# TFT.net
KiCad netlist of a schematic drawn in Altium Designer
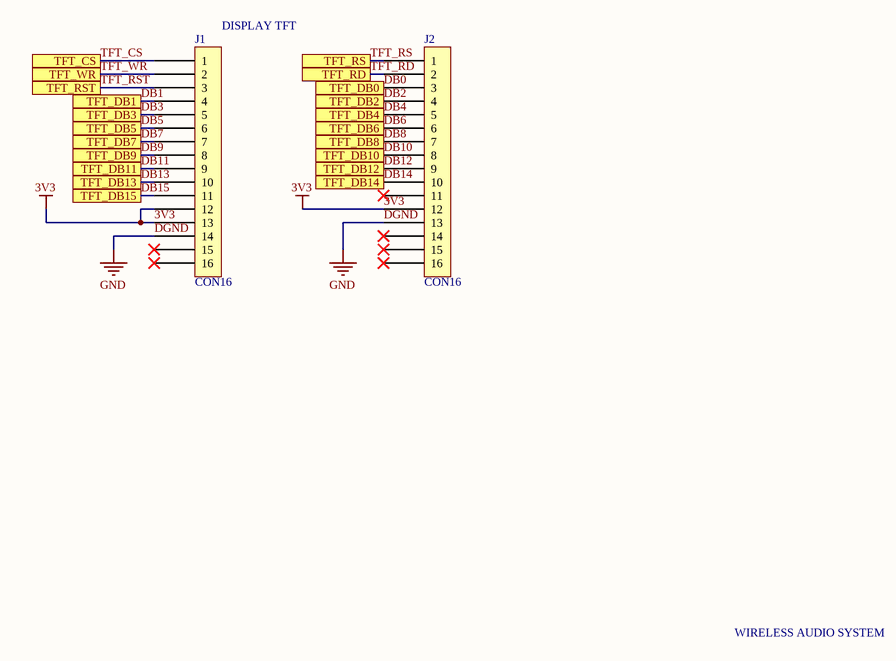
[diagram p0: TFT.SchDoc]

(export (version "E")
  (design (tool "Eeschema 10.0.6"))
  (components
    (comp (ref "J1")
      (value "CON16")
      (footprint "HDR1X16")
      (libsource (lib "Miscellaneous Connectors") (part "CON16"))
    )
    (comp (ref "J2")
      (value "CON16")
      (footprint "HDR1X16")
      (libsource (lib "Miscellaneous Connectors") (part "CON16"))
    )
  )
  (nets
    (net (code "1") (name "/DB0") (class "Default")
      (node (ref "J2") (pin "3") (pinfunction "3_3") (pintype "passive"))
    )
    (net (code "2") (name "/DB1") (class "Default")
      (node (ref "J1") (pin "4") (pinfunction "4_4") (pintype "passive"))
    )
    (net (code "3") (name "/DB2") (class "Default")
      (node (ref "J2") (pin "4") (pinfunction "4_4") (pintype "passive"))
    )
    (net (code "4") (name "/DB3") (class "Default")
      (node (ref "J1") (pin "5") (pinfunction "5_5") (pintype "passive"))
    )
    (net (code "5") (name "/DB4") (class "Default")
      (node (ref "J2") (pin "5") (pinfunction "5_5") (pintype "passive"))
    )
    (net (code "6") (name "/DB5") (class "Default")
      (node (ref "J1") (pin "6") (pinfunction "6_6") (pintype "passive"))
    )
    (net (code "7") (name "/DB6") (class "Default")
      (node (ref "J2") (pin "6") (pinfunction "6_6") (pintype "passive"))
    )
    (net (code "8") (name "/DB7") (class "Default")
      (node (ref "J1") (pin "7") (pinfunction "7_7") (pintype "passive"))
    )
    (net (code "9") (name "/DB8") (class "Default")
      (node (ref "J2") (pin "7") (pinfunction "7_7") (pintype "passive"))
    )
    (net (code "10") (name "/DB9") (class "Default")
      (node (ref "J1") (pin "8") (pinfunction "8_8") (pintype "passive"))
    )
    (net (code "11") (name "/DB10") (class "Default")
      (node (ref "J2") (pin "8") (pinfunction "8_8") (pintype "passive"))
    )
    (net (code "12") (name "/DB11") (class "Default")
      (node (ref "J1") (pin "9") (pinfunction "9_9") (pintype "passive"))
    )
    (net (code "13") (name "/DB12") (class "Default")
      (node (ref "J2") (pin "9") (pinfunction "9_9") (pintype "passive"))
    )
    (net (code "14") (name "/DB13") (class "Default")
      (node (ref "J1") (pin "10") (pinfunction "10_10") (pintype "passive"))
    )
    (net (code "15") (name "/DB14") (class "Default")
      (node (ref "J2") (pin "10") (pinfunction "10_10") (pintype "passive"))
    )
    (net (code "16") (name "/DB15") (class "Default")
      (node (ref "J1") (pin "11") (pinfunction "11_11") (pintype "passive"))
    )
    (net (code "17") (name "/TFT_CS") (class "Default")
      (node (ref "J1") (pin "1") (pinfunction "1_1") (pintype "passive"))
    )
    (net (code "18") (name "/TFT_RD") (class "Default")
      (node (ref "J2") (pin "2") (pinfunction "2_2") (pintype "passive"))
    )
    (net (code "19") (name "/TFT_RS") (class "Default")
      (node (ref "J2") (pin "1") (pinfunction "1_1") (pintype "passive"))
    )
    (net (code "20") (name "/TFT_RST") (class "Default")
      (node (ref "J1") (pin "3") (pinfunction "3_3") (pintype "passive"))
    )
    (net (code "21") (name "/TFT_WR") (class "Default")
      (node (ref "J1") (pin "2") (pinfunction "2_2") (pintype "passive"))
    )
    (net (code "22") (name "3V3") (class "Default")
      (node (ref "J1") (pin "12") (pinfunction "12_12") (pintype "passive"))
      (node (ref "J1") (pin "13") (pinfunction "13_13") (pintype "passive"))
      (node (ref "J2") (pin "12") (pinfunction "12_12") (pintype "passive"))
    )
    (net (code "23") (name "GND") (class "Default")
      (node (ref "J1") (pin "14") (pinfunction "14_14") (pintype "passive"))
      (node (ref "J2") (pin "13") (pinfunction "13_13") (pintype "passive"))
    )
    (net (code "24") (name "unconnected-(J1-Pad15)") (class "Default")
      (node (ref "J1") (pin "15") (pinfunction "15_15") (pintype "passive+no_connect"))
    )
    (net (code "25") (name "unconnected-(J1-Pad16)") (class "Default")
      (node (ref "J1") (pin "16") (pinfunction "16_16") (pintype "passive+no_connect"))
    )
    (net (code "26") (name "unconnected-(J2-Pad11)") (class "Default")
      (node (ref "J2") (pin "11") (pinfunction "11_11") (pintype "passive+no_connect"))
    )
    (net (code "27") (name "unconnected-(J2-Pad14)") (class "Default")
      (node (ref "J2") (pin "14") (pinfunction "14_14") (pintype "passive+no_connect"))
    )
    (net (code "28") (name "unconnected-(J2-Pad15)") (class "Default")
      (node (ref "J2") (pin "15") (pinfunction "15_15") (pintype "passive+no_connect"))
    )
    (net (code "29") (name "unconnected-(J2-Pad16)") (class "Default")
      (node (ref "J2") (pin "16") (pinfunction "16_16") (pintype "passive+no_connect"))
    )
  )
)
